# basis.net
KiCad netlist of a schematic drawn in EAGLE
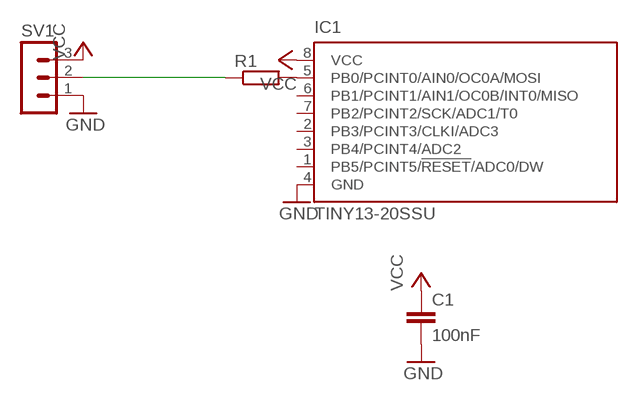
[diagram p0: schematic, sheet 1]

(export (version "E")
  (design (tool "Eeschema 10.0.6"))
  (components
    (comp (ref "C1")
      (value "100nF")
      (footprint "eagle-import:C0603")
      (libsource (lib "eagle-import") (part "C-EUC0603"))
    )
    (comp (ref "IC1")
      (value "TINY13-20SSU")
      (footprint "eagle-import:8S1")
      (fields (field (name "MPN") "ATTINY13-20SSU"))
      (libsource (lib "eagle-import") (part "TINY13SSU-20"))
    )
    (comp (ref "R1")
      (value "R-EU_R0805")
      (footprint "eagle-import:R0805")
      (libsource (lib "eagle-import") (part "R-EU_R0805"))
    )
    (comp (ref "SV1")
      (value "MA03-1")
      (footprint "eagle-import:MA03-1")
      (libsource (lib "eagle-import") (part "MA03-1"))
    )
  )
  (nets
    (net (code "1") (name "GND") (class "Default")
      (node (ref "C1") (pin "2") (pinfunction "2_2") (pintype "passive"))
      (node (ref "IC1") (pin "4") (pinfunction "GND_4") (pintype "power_in"))
      (node (ref "SV1") (pin "1") (pinfunction "1_1") (pintype "passive"))
    )
    (net (code "2") (name "Net-(IC1-PB0{slash}PCINT0{slash}AIN0{slash}OC0A{slash}MOSI)") (class "Default")
      (node (ref "IC1") (pin "5") (pinfunction "PB0/PCINT0/AIN0/OC0A/MOSI_5") (pintype "bidirectional"))
      (node (ref "R1") (pin "2") (pinfunction "2_2") (pintype "passive"))
    )
    (net (code "3") (name "Net-(R1-Pad1)") (class "Default")
      (node (ref "R1") (pin "1") (pinfunction "1_1") (pintype "passive"))
      (node (ref "SV1") (pin "2") (pinfunction "2_2") (pintype "passive"))
    )
    (net (code "4") (name "VCC") (class "Default")
      (node (ref "C1") (pin "1") (pinfunction "1_1") (pintype "passive"))
      (node (ref "IC1") (pin "8") (pinfunction "VCC_8") (pintype "power_in"))
      (node (ref "SV1") (pin "3") (pinfunction "3_3") (pintype "passive"))
    )
    (net (code "5") (name "unconnected-(IC1-PB1{slash}PCINT1{slash}AIN1{slash}OC0B{slash}INT0{slash}MISO-Pad6)") (class "Default")
      (node (ref "IC1") (pin "6") (pinfunction "PB1/PCINT1/AIN1/OC0B/INT0/MISO_6") (pintype "bidirectional"))
    )
    (net (code "6") (name "unconnected-(IC1-PB2{slash}PCINT2{slash}SCK{slash}ADC1{slash}T0-Pad7)") (class "Default")
      (node (ref "IC1") (pin "7") (pinfunction "PB2/PCINT2/SCK/ADC1/T0_7") (pintype "bidirectional"))
    )
    (net (code "7") (name "unconnected-(IC1-PB3{slash}PCINT3{slash}CLKI{slash}ADC3-Pad2)") (class "Default")
      (node (ref "IC1") (pin "2") (pinfunction "PB3/PCINT3/CLKI/ADC3_2") (pintype "bidirectional"))
    )
    (net (code "8") (name "unconnected-(IC1-PB4{slash}PCINT4{slash}ADC2-Pad3)") (class "Default")
      (node (ref "IC1") (pin "3") (pinfunction "PB4/PCINT4/ADC2_3") (pintype "bidirectional"))
    )
    (net (code "9") (name "unconnected-(IC1-PB5{slash}PCINT5{slash}~{RESET}{slash}ADC0{slash}DW-Pad1)") (class "Default")
      (node (ref "IC1") (pin "1") (pinfunction "PB5/PCINT5/~{RESET}/ADC0/DW_1") (pintype "bidirectional"))
    )
  )
)
